# SCH_Arduino_Nano_ESP32_CapibaraZero_2024.net
KiCad netlist of a schematic drawn in EasyEDA
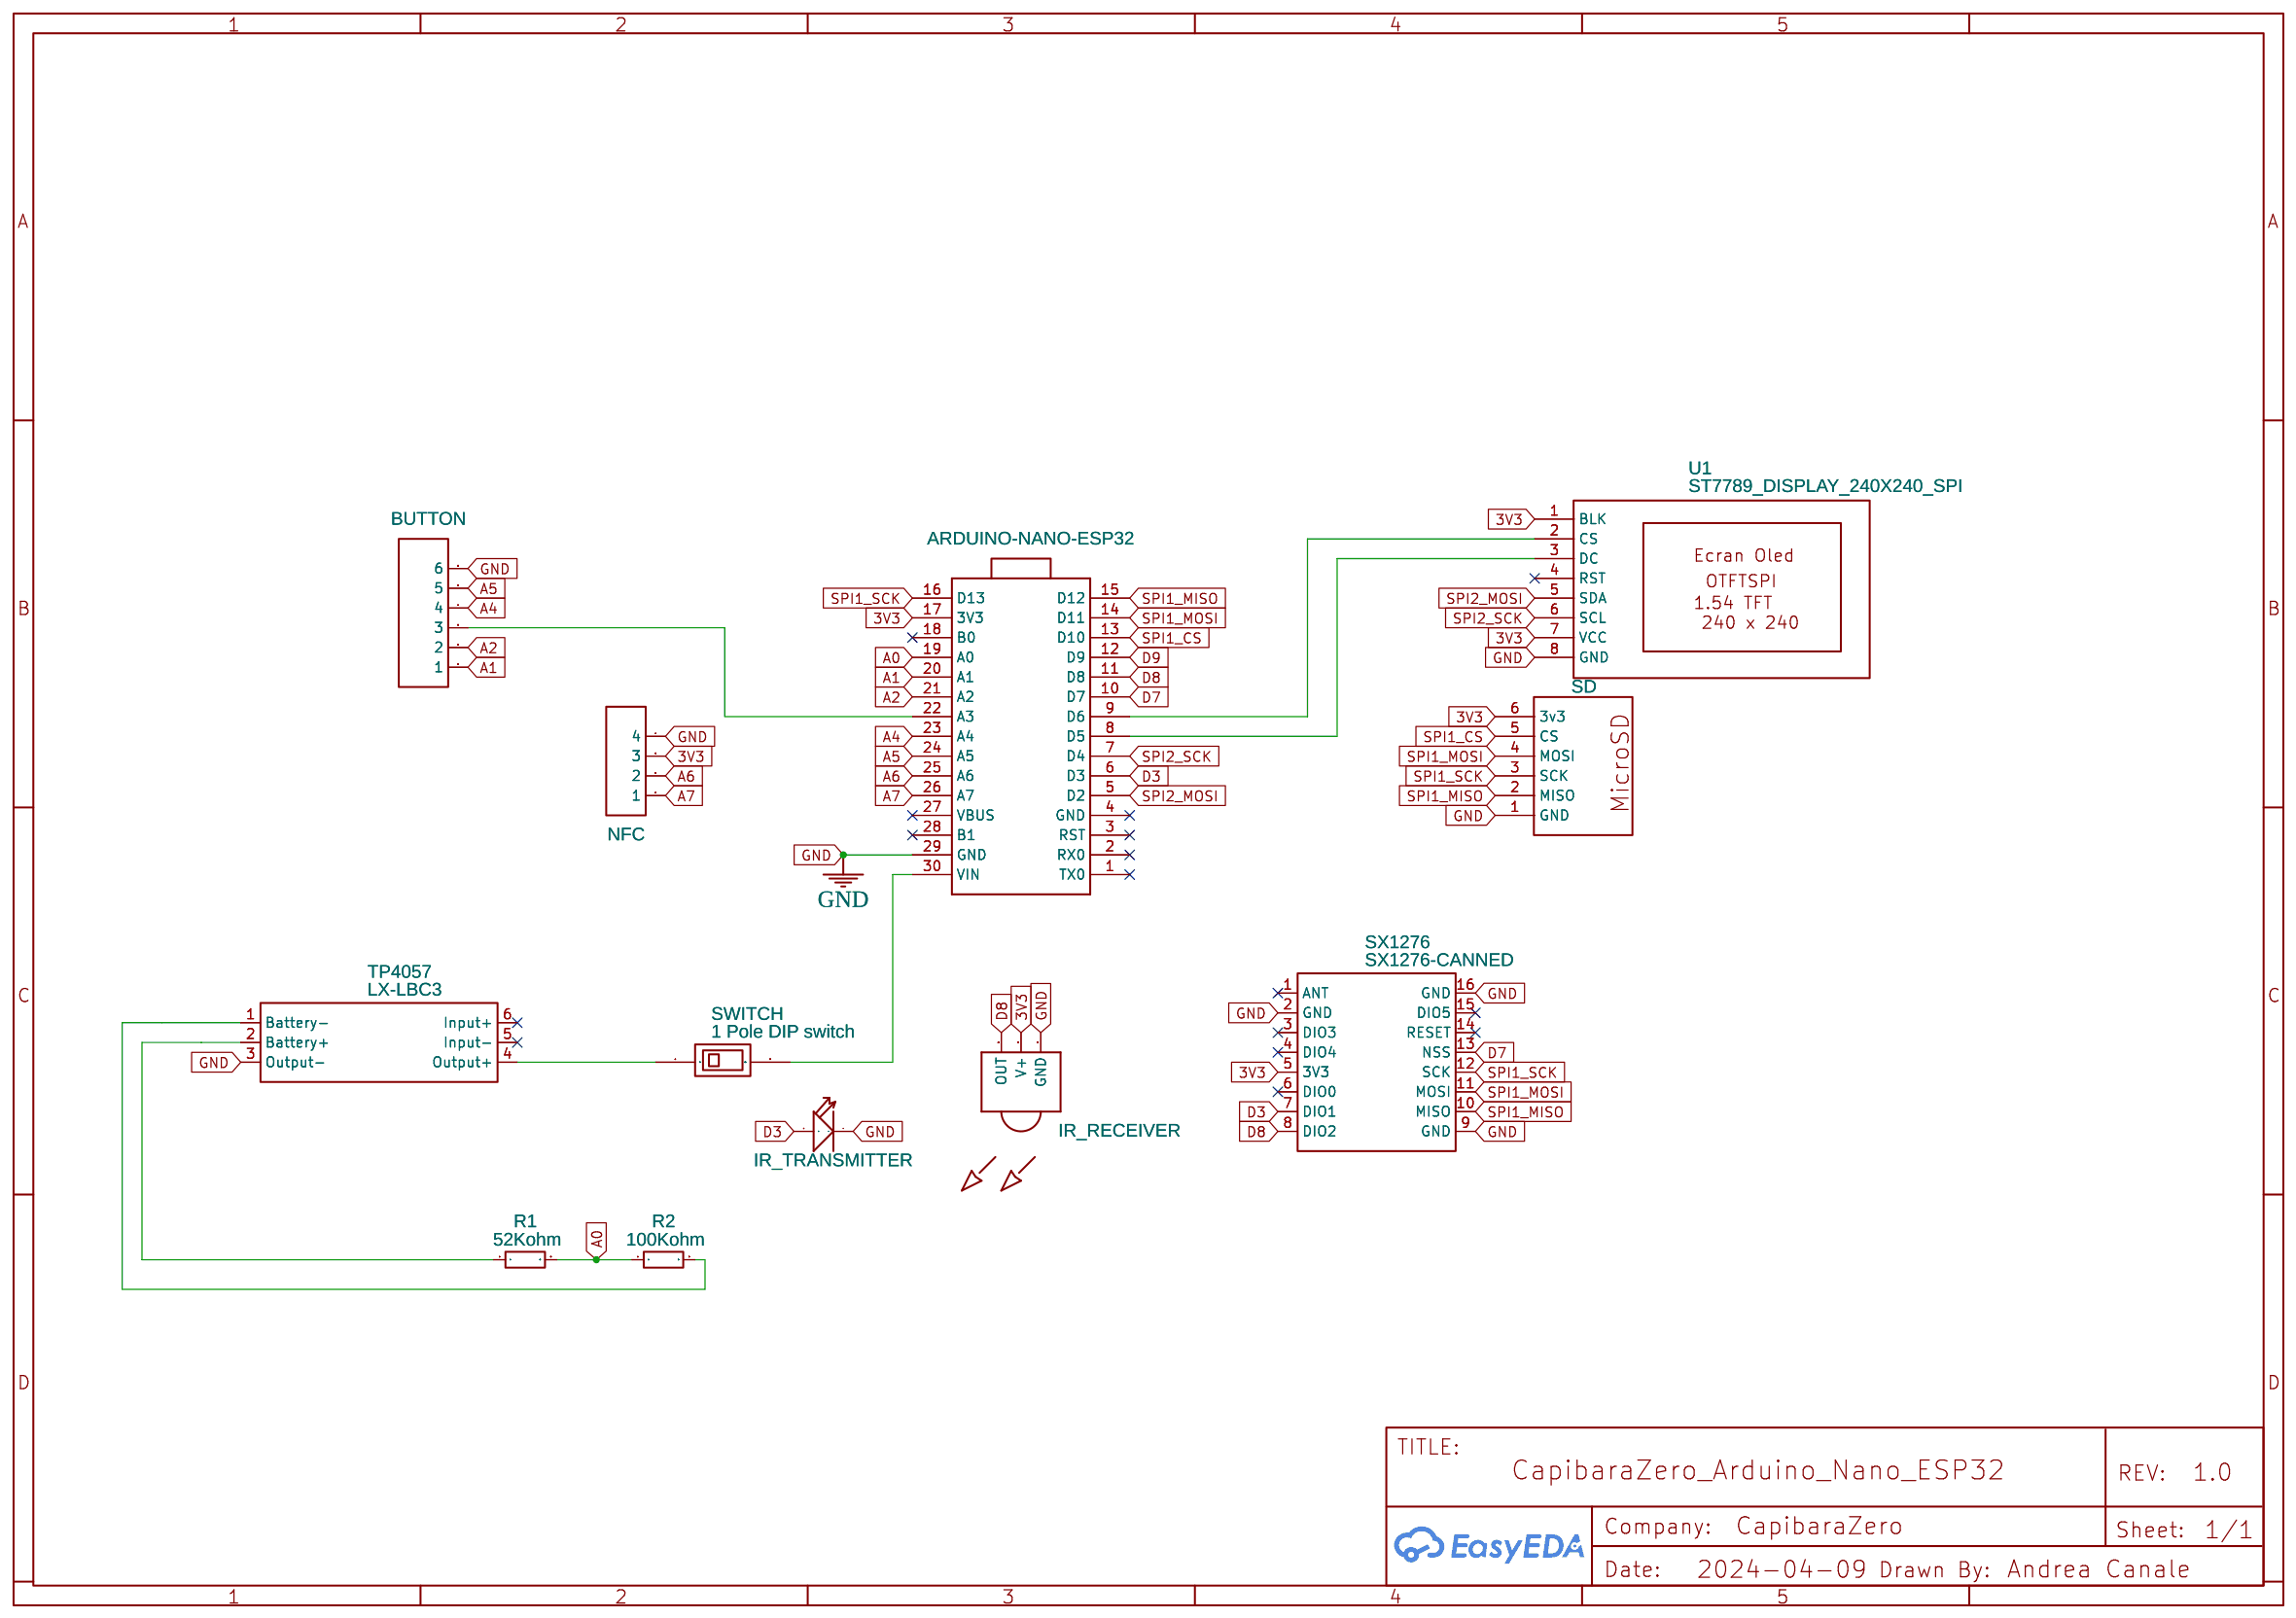
[diagram p0: MainScheme]
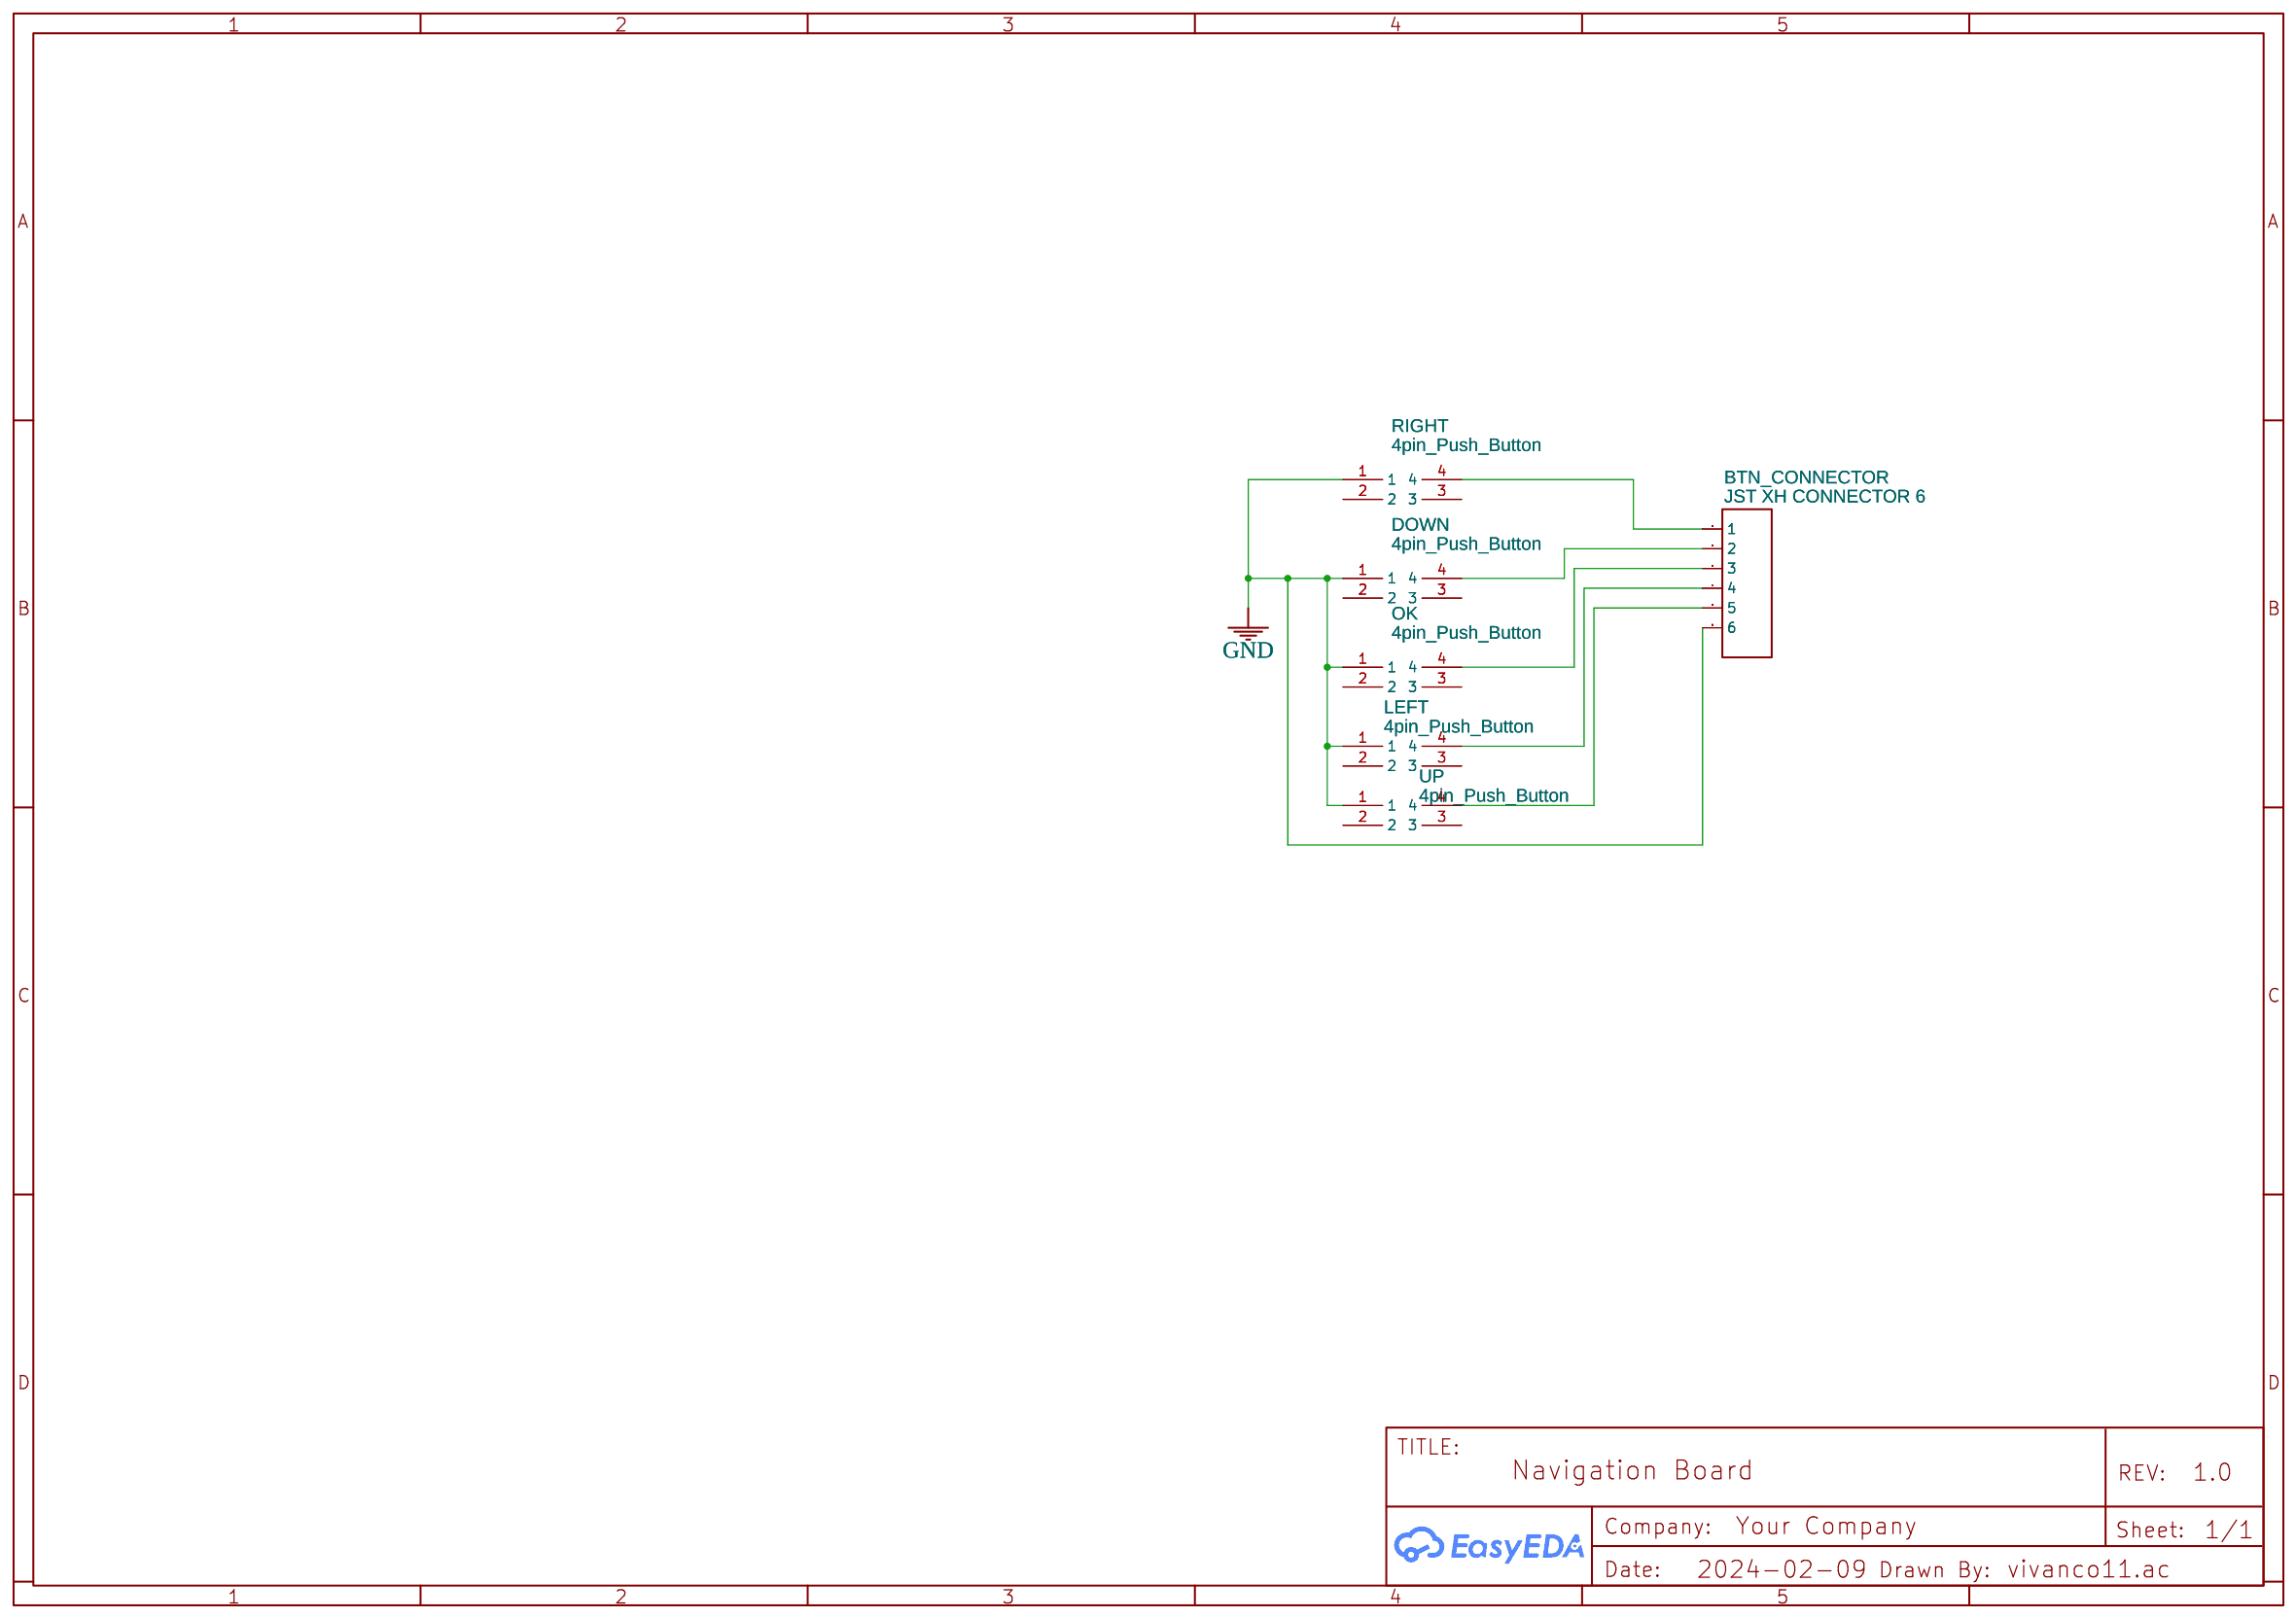
[diagram p1: Navigation_board]

(export (version "E")
  (design (tool "Eeschema 10.0.6"))
  (components
    (comp (ref "ARDUINO-NANO-ESP32")
      (value "ARDUINO-NANO-ESP32")
      (fields (field (name "Manufacturer") "Arduino"))
      (libsource (lib "") (part "ARDUINO-NANO-ESP32"))
    )
    (comp (ref "BUTTON")
      (value "BTN Connector")
      (fields (field (name "Manufacturer Part") "JST_XH CONNECTOR"))
      (libsource (lib "") (part "JST XH CONNECTOR 6"))
    )
    (comp (ref "IR_RECEIVER") (value "IR Receiver") (libsource (lib "") (part "IR TRANSMITTER")))
    (comp (ref "IR_TRANSMITTER")
      (value "DIP-IR-LED-940NM(2P-D5MM)")
      (fields (field (name "Manufacturer Part") "IR523B-W60W1"))
      (libsource (lib "") (part "DIP-IR-LED-940NM(2P-D5MM)"))
    )
    (comp (ref "NFC")
      (value "NFC Connector")
      (fields (field (name "Manufacturer Part") "JST_XH CONNECTOR"))
      (libsource (lib "") (part "JST XH CONNECTOR 4"))
    )
    (comp (ref "R1")
      (value "52Kohm")
      (fields
        (field (name "Manufacturer Part") "EWWR0001J20R0T9")
        (field (name "Manufacturer") "ResistorToday")
      )
      (libsource (lib "") (part "Resistor Normal"))
    )
    (comp (ref "R2")
      (value "100Kohm")
      (fields
        (field (name "Manufacturer Part") "EWWR0001J20R0T9")
        (field (name "Manufacturer") "ResistorToday")
      )
      (libsource (lib "") (part "Resistor Normal"))
    )
    (comp (ref "SD") (value "MicroSDSPI") (libsource (lib "") (part "MicroSDSPI")))
    (comp (ref "SWITCH") (value "1 Pole DIP switch") (libsource (lib "") (part "1 Pole DIP switch")))
    (comp (ref "SX1276")
      (value "SX1276-CANNED")
      (fields (field (name "Manufacturer Part") "LoRa1276-C1") (field (name "Manufacturer") "G-NiceRF"))
      (libsource (lib "") (part "SX1276-CANNED"))
    )
    (comp (ref "TP4057") (value "LX-LBC3") (libsource (lib "") (part "LX-LBC3")))
    (comp (ref "U1")
      (value "ST7789_DISPLAY_240X240_SPI")
      (libsource (lib "") (part "ST7789_DISPLAY_240X240_SPI"))
    )
    (comp (ref "BTN_CONNECTOR")
      (value "JST XH CONNECTOR 6")
      (fields (field (name "Manufacturer Part") "JST_XH CONNECTOR"))
      (libsource (lib "") (part "JST XH CONNECTOR 6"))
    )
    (comp (ref "DOWN") (value "4pin_Push_Button") (libsource (lib "") (part "4pin_Push_Button_3")))
    (comp (ref "LEFT") (value "4pin_Push_Button") (libsource (lib "") (part "4pin_Push_Button_1")))
    (comp (ref "OK") (value "4pin_Push_Button") (libsource (lib "") (part "4pin_Push_Button_4")))
    (comp (ref "RIGHT") (value "4pin_Push_Button") (libsource (lib "") (part "4pin_Push_Button_2")))
    (comp (ref "UP") (value "4pin_Push_Button") (libsource (lib "") (part "4pin_Push_Button")))
  )
  (nets
    (net (code "1") (name "3V3") (class "Default")
      (node (ref "ARDUINO-NANO-ESP32") (pin "17") (pinfunction "3V3_17") (pintype "unspecified"))
      (node (ref "IR_RECEIVER") (pin "VCC") (pinfunction "V+_VCC") (pintype "unspecified"))
      (node (ref "NFC") (pin "3") (pinfunction "3_3") (pintype "unspecified"))
      (node (ref "SD") (pin "6") (pinfunction "3v3_6") (pintype "unspecified"))
      (node (ref "SX1276") (pin "5") (pinfunction "3V3_5") (pintype "unspecified"))
      (node (ref "U1") (pin "1") (pinfunction "BLK_1") (pintype "unspecified"))
      (node (ref "U1") (pin "7") (pinfunction "VCC_7") (pintype "unspecified"))
    )
    (net (code "2") (name "A0") (class "Default")
      (node (ref "ARDUINO-NANO-ESP32") (pin "19") (pinfunction "A0_19") (pintype "unspecified"))
      (node (ref "R1") (pin "2") (pinfunction "2_2") (pintype "unspecified"))
      (node (ref "R2") (pin "1") (pinfunction "1_1") (pintype "unspecified"))
    )
    (net (code "3") (name "A1") (class "Default")
      (node (ref "ARDUINO-NANO-ESP32") (pin "20") (pinfunction "A1_20") (pintype "unspecified"))
      (node (ref "BUTTON") (pin "1") (pinfunction "1_1") (pintype "unspecified"))
    )
    (net (code "4") (name "A2") (class "Default")
      (node (ref "ARDUINO-NANO-ESP32") (pin "21") (pinfunction "A2_21") (pintype "unspecified"))
      (node (ref "BUTTON") (pin "2") (pinfunction "2_2") (pintype "unspecified"))
    )
    (net (code "5") (name "A4") (class "Default")
      (node (ref "ARDUINO-NANO-ESP32") (pin "23") (pinfunction "A4_23") (pintype "unspecified"))
      (node (ref "BUTTON") (pin "4") (pinfunction "4_4") (pintype "unspecified"))
    )
    (net (code "6") (name "A5") (class "Default")
      (node (ref "ARDUINO-NANO-ESP32") (pin "24") (pinfunction "A5_24") (pintype "unspecified"))
      (node (ref "BUTTON") (pin "5") (pinfunction "5_5") (pintype "unspecified"))
    )
    (net (code "7") (name "A6") (class "Default")
      (node (ref "ARDUINO-NANO-ESP32") (pin "25") (pinfunction "A6_25") (pintype "unspecified"))
      (node (ref "NFC") (pin "2") (pinfunction "2_2") (pintype "unspecified"))
    )
    (net (code "8") (name "A7") (class "Default")
      (node (ref "ARDUINO-NANO-ESP32") (pin "26") (pinfunction "A7_26") (pintype "unspecified"))
      (node (ref "NFC") (pin "1") (pinfunction "1_1") (pintype "unspecified"))
    )
    (net (code "9") (name "D3") (class "Default")
      (node (ref "ARDUINO-NANO-ESP32") (pin "6") (pinfunction "D3_6") (pintype "unspecified"))
      (node (ref "IR_TRANSMITTER") (pin "+") (pinfunction "+_+") (pintype "unspecified"))
      (node (ref "SX1276") (pin "7") (pinfunction "DIO1_7") (pintype "unspecified"))
    )
    (net (code "10") (name "D7") (class "Default")
      (node (ref "ARDUINO-NANO-ESP32") (pin "10") (pinfunction "D7_10") (pintype "unspecified"))
      (node (ref "SX1276") (pin "13") (pinfunction "NSS_13") (pintype "unspecified"))
    )
    (net (code "11") (name "D8") (class "Default")
      (node (ref "ARDUINO-NANO-ESP32") (pin "11") (pinfunction "D8_11") (pintype "unspecified"))
      (node (ref "IR_RECEIVER") (pin "OUT") (pinfunction "OUT_OUT") (pintype "unspecified"))
      (node (ref "SX1276") (pin "8") (pinfunction "DIO2_8") (pintype "unspecified"))
    )
    (net (code "12") (name "D9") (class "Default")
      (node (ref "ARDUINO-NANO-ESP32") (pin "12") (pinfunction "D9_12") (pintype "unspecified"))
    )
    (net (code "13") (name "GND") (class "Default")
      (node (ref "ARDUINO-NANO-ESP32") (pin "29") (pinfunction "GND_29") (pintype "unspecified"))
      (node (ref "BTN_CONNECTOR") (pin "6") (pinfunction "6_6") (pintype "unspecified"))
      (node (ref "BUTTON") (pin "6") (pinfunction "6_6") (pintype "unspecified"))
      (node (ref "DOWN") (pin "1") (pinfunction "1_1") (pintype "unspecified"))
      (node (ref "IR_RECEIVER") (pin "GND") (pinfunction "GND_GND") (pintype "unspecified"))
      (node (ref "IR_TRANSMITTER") (pin "-") (pinfunction "-_-") (pintype "unspecified"))
      (node (ref "LEFT") (pin "1") (pinfunction "1_1") (pintype "unspecified"))
      (node (ref "NFC") (pin "4") (pinfunction "4_4") (pintype "unspecified"))
      (node (ref "OK") (pin "1") (pinfunction "1_1") (pintype "unspecified"))
      (node (ref "RIGHT") (pin "1") (pinfunction "1_1") (pintype "unspecified"))
      (node (ref "SD") (pin "1") (pinfunction "GND_1") (pintype "unspecified"))
      (node (ref "SX1276") (pin "16") (pinfunction "GND_16") (pintype "unspecified"))
      (node (ref "SX1276") (pin "2") (pinfunction "GND_2") (pintype "unspecified"))
      (node (ref "SX1276") (pin "9") (pinfunction "GND_9") (pintype "unspecified"))
      (node (ref "TP4057") (pin "3") (pinfunction "Output-_3") (pintype "unspecified"))
      (node (ref "U1") (pin "8") (pinfunction "GND_8") (pintype "unspecified"))
      (node (ref "UP") (pin "1") (pinfunction "1_1") (pintype "unspecified"))
    )
    (net (code "14") (name "Net-(ARDUINO-NANO-ESP32-A3)") (class "Default")
      (node (ref "ARDUINO-NANO-ESP32") (pin "22") (pinfunction "A3_22") (pintype "unspecified"))
      (node (ref "BUTTON") (pin "3") (pinfunction "3_3") (pintype "unspecified"))
    )
    (net (code "15") (name "Net-(ARDUINO-NANO-ESP32-D5)") (class "Default")
      (node (ref "ARDUINO-NANO-ESP32") (pin "8") (pinfunction "D5_8") (pintype "unspecified"))
      (node (ref "U1") (pin "3") (pinfunction "DC_3") (pintype "unspecified"))
    )
    (net (code "16") (name "Net-(ARDUINO-NANO-ESP32-D6)") (class "Default")
      (node (ref "ARDUINO-NANO-ESP32") (pin "9") (pinfunction "D6_9") (pintype "unspecified"))
      (node (ref "U1") (pin "2") (pinfunction "CS_2") (pintype "unspecified"))
    )
    (net (code "17") (name "Net-(ARDUINO-NANO-ESP32-VIN)") (class "Default")
      (node (ref "ARDUINO-NANO-ESP32") (pin "30") (pinfunction "VIN_30") (pintype "unspecified"))
      (node (ref "SWITCH") (pin "2") (pinfunction "OUT_2") (pintype "unspecified"))
    )
    (net (code "18") (name "Net-(BTN_CONNECTOR-Pad1)") (class "Default")
      (node (ref "BTN_CONNECTOR") (pin "1") (pinfunction "1_1") (pintype "unspecified"))
      (node (ref "RIGHT") (pin "4") (pinfunction "4_4") (pintype "unspecified"))
    )
    (net (code "19") (name "Net-(BTN_CONNECTOR-Pad2)") (class "Default")
      (node (ref "BTN_CONNECTOR") (pin "2") (pinfunction "2_2") (pintype "unspecified"))
      (node (ref "DOWN") (pin "4") (pinfunction "4_4") (pintype "unspecified"))
    )
    (net (code "20") (name "Net-(BTN_CONNECTOR-Pad3)") (class "Default")
      (node (ref "BTN_CONNECTOR") (pin "3") (pinfunction "3_3") (pintype "unspecified"))
      (node (ref "OK") (pin "4") (pinfunction "4_4") (pintype "unspecified"))
    )
    (net (code "21") (name "Net-(BTN_CONNECTOR-Pad4)") (class "Default")
      (node (ref "BTN_CONNECTOR") (pin "4") (pinfunction "4_4") (pintype "unspecified"))
      (node (ref "LEFT") (pin "4") (pinfunction "4_4") (pintype "unspecified"))
    )
    (net (code "22") (name "Net-(BTN_CONNECTOR-Pad5)") (class "Default")
      (node (ref "BTN_CONNECTOR") (pin "5") (pinfunction "5_5") (pintype "unspecified"))
      (node (ref "UP") (pin "4") (pinfunction "4_4") (pintype "unspecified"))
    )
    (net (code "23") (name "Net-(SWITCH-IN)") (class "Default")
      (node (ref "SWITCH") (pin "1") (pinfunction "IN_1") (pintype "unspecified"))
      (node (ref "TP4057") (pin "4") (pinfunction "Output+_4") (pintype "unspecified"))
    )
    (net (code "24") (name "Net-(TP4057-Battery+)") (class "Default")
      (node (ref "R1") (pin "1") (pinfunction "1_1") (pintype "unspecified"))
      (node (ref "TP4057") (pin "2") (pinfunction "Battery+_2") (pintype "unspecified"))
    )
    (net (code "25") (name "Net-(TP4057-Battery-)") (class "Default")
      (node (ref "R2") (pin "2") (pinfunction "2_2") (pintype "unspecified"))
      (node (ref "TP4057") (pin "1") (pinfunction "Battery-_1") (pintype "unspecified"))
    )
    (net (code "26") (name "SPI1_CS") (class "Default")
      (node (ref "ARDUINO-NANO-ESP32") (pin "13") (pinfunction "D10_13") (pintype "unspecified"))
      (node (ref "SD") (pin "5") (pinfunction "CS_5") (pintype "unspecified"))
    )
    (net (code "27") (name "SPI1_MISO") (class "Default")
      (node (ref "ARDUINO-NANO-ESP32") (pin "15") (pinfunction "D12_15") (pintype "unspecified"))
      (node (ref "SD") (pin "2") (pinfunction "MISO_2") (pintype "unspecified"))
      (node (ref "SX1276") (pin "10") (pinfunction "MISO_10") (pintype "unspecified"))
    )
    (net (code "28") (name "SPI1_MOSI") (class "Default")
      (node (ref "ARDUINO-NANO-ESP32") (pin "14") (pinfunction "D11_14") (pintype "unspecified"))
      (node (ref "SD") (pin "4") (pinfunction "MOSI_4") (pintype "unspecified"))
      (node (ref "SX1276") (pin "11") (pinfunction "MOSI_11") (pintype "unspecified"))
    )
    (net (code "29") (name "SPI1_SCK") (class "Default")
      (node (ref "ARDUINO-NANO-ESP32") (pin "16") (pinfunction "D13_16") (pintype "unspecified"))
      (node (ref "SD") (pin "3") (pinfunction "SCK_3") (pintype "unspecified"))
      (node (ref "SX1276") (pin "12") (pinfunction "SCK_12") (pintype "unspecified"))
    )
    (net (code "30") (name "SPI2_MOSI") (class "Default")
      (node (ref "ARDUINO-NANO-ESP32") (pin "5") (pinfunction "D2_5") (pintype "unspecified"))
      (node (ref "U1") (pin "5") (pinfunction "SDA_5") (pintype "unspecified"))
    )
    (net (code "31") (name "SPI2_SCK") (class "Default")
      (node (ref "ARDUINO-NANO-ESP32") (pin "7") (pinfunction "D4_7") (pintype "unspecified"))
      (node (ref "U1") (pin "6") (pinfunction "SCL_6") (pintype "unspecified"))
    )
    (net (code "32") (name "unconnected-(ARDUINO-NANO-ESP32-B0-Pad18)") (class "Default")
      (node (ref "ARDUINO-NANO-ESP32") (pin "18") (pinfunction "B0_18") (pintype "unspecified+no_connect"))
    )
    (net (code "33") (name "unconnected-(ARDUINO-NANO-ESP32-B1-Pad28)") (class "Default")
      (node (ref "ARDUINO-NANO-ESP32") (pin "28") (pinfunction "B1_28") (pintype "unspecified+no_connect"))
    )
    (net (code "34") (name "unconnected-(ARDUINO-NANO-ESP32-GND-Pad4)") (class "Default")
      (node (ref "ARDUINO-NANO-ESP32") (pin "4") (pinfunction "GND_4") (pintype "unspecified+no_connect"))
    )
    (net (code "35") (name "unconnected-(ARDUINO-NANO-ESP32-RST-Pad3)") (class "Default")
      (node (ref "ARDUINO-NANO-ESP32") (pin "3") (pinfunction "RST_3") (pintype "unspecified+no_connect"))
    )
    (net (code "36") (name "unconnected-(ARDUINO-NANO-ESP32-RX0-Pad2)") (class "Default")
      (node (ref "ARDUINO-NANO-ESP32") (pin "2") (pinfunction "RX0_2") (pintype "unspecified+no_connect"))
    )
    (net (code "37") (name "unconnected-(ARDUINO-NANO-ESP32-TX0-Pad1)") (class "Default")
      (node (ref "ARDUINO-NANO-ESP32") (pin "1") (pinfunction "TX0_1") (pintype "unspecified+no_connect"))
    )
    (net (code "38") (name "unconnected-(ARDUINO-NANO-ESP32-VBUS-Pad27)") (class "Default")
      (node (ref "ARDUINO-NANO-ESP32") (pin "27") (pinfunction "VBUS_27") (pintype "unspecified+no_connect"))
    )
    (net (code "39") (name "unconnected-(DOWN-Pad2)") (class "Default")
      (node (ref "DOWN") (pin "2") (pinfunction "2_2") (pintype "unspecified"))
    )
    (net (code "40") (name "unconnected-(DOWN-Pad3)") (class "Default")
      (node (ref "DOWN") (pin "3") (pinfunction "3_3") (pintype "unspecified"))
    )
    (net (code "41") (name "unconnected-(LEFT-Pad2)") (class "Default")
      (node (ref "LEFT") (pin "2") (pinfunction "2_2") (pintype "unspecified"))
    )
    (net (code "42") (name "unconnected-(LEFT-Pad3)") (class "Default")
      (node (ref "LEFT") (pin "3") (pinfunction "3_3") (pintype "unspecified"))
    )
    (net (code "43") (name "unconnected-(OK-Pad2)") (class "Default")
      (node (ref "OK") (pin "2") (pinfunction "2_2") (pintype "unspecified"))
    )
    (net (code "44") (name "unconnected-(OK-Pad3)") (class "Default")
      (node (ref "OK") (pin "3") (pinfunction "3_3") (pintype "unspecified"))
    )
    (net (code "45") (name "unconnected-(RIGHT-Pad2)") (class "Default")
      (node (ref "RIGHT") (pin "2") (pinfunction "2_2") (pintype "unspecified"))
    )
    (net (code "46") (name "unconnected-(RIGHT-Pad3)") (class "Default")
      (node (ref "RIGHT") (pin "3") (pinfunction "3_3") (pintype "unspecified"))
    )
    (net (code "47") (name "unconnected-(SX1276-ANT-Pad1)") (class "Default")
      (node (ref "SX1276") (pin "1") (pinfunction "ANT_1") (pintype "unspecified+no_connect"))
    )
    (net (code "48") (name "unconnected-(SX1276-DIO0-Pad6)") (class "Default")
      (node (ref "SX1276") (pin "6") (pinfunction "DIO0_6") (pintype "unspecified+no_connect"))
    )
    (net (code "49") (name "unconnected-(SX1276-DIO3-Pad3)") (class "Default")
      (node (ref "SX1276") (pin "3") (pinfunction "DIO3_3") (pintype "unspecified+no_connect"))
    )
    (net (code "50") (name "unconnected-(SX1276-DIO4-Pad4)") (class "Default")
      (node (ref "SX1276") (pin "4") (pinfunction "DIO4_4") (pintype "unspecified+no_connect"))
    )
    (net (code "51") (name "unconnected-(SX1276-DIO5-Pad15)") (class "Default")
      (node (ref "SX1276") (pin "15") (pinfunction "DIO5_15") (pintype "unspecified+no_connect"))
    )
    (net (code "52") (name "unconnected-(SX1276-RESET-Pad14)") (class "Default")
      (node (ref "SX1276") (pin "14") (pinfunction "RESET_14") (pintype "unspecified+no_connect"))
    )
    (net (code "53") (name "unconnected-(TP4057-Input+-Pad6)") (class "Default")
      (node (ref "TP4057") (pin "6") (pinfunction "Input+_6") (pintype "unspecified+no_connect"))
    )
    (net (code "54") (name "unconnected-(TP4057-Input--Pad5)") (class "Default")
      (node (ref "TP4057") (pin "5") (pinfunction "Input-_5") (pintype "unspecified+no_connect"))
    )
    (net (code "55") (name "unconnected-(U1-RST-Pad4)") (class "Default")
      (node (ref "U1") (pin "4") (pinfunction "RST_4") (pintype "unspecified+no_connect"))
    )
    (net (code "56") (name "unconnected-(UP-Pad2)") (class "Default")
      (node (ref "UP") (pin "2") (pinfunction "2_2") (pintype "unspecified"))
    )
    (net (code "57") (name "unconnected-(UP-Pad3)") (class "Default")
      (node (ref "UP") (pin "3") (pinfunction "3_3") (pintype "unspecified"))
    )
  )
)
